# OTHERS.net
KiCad netlist of a schematic drawn in Altium Designer
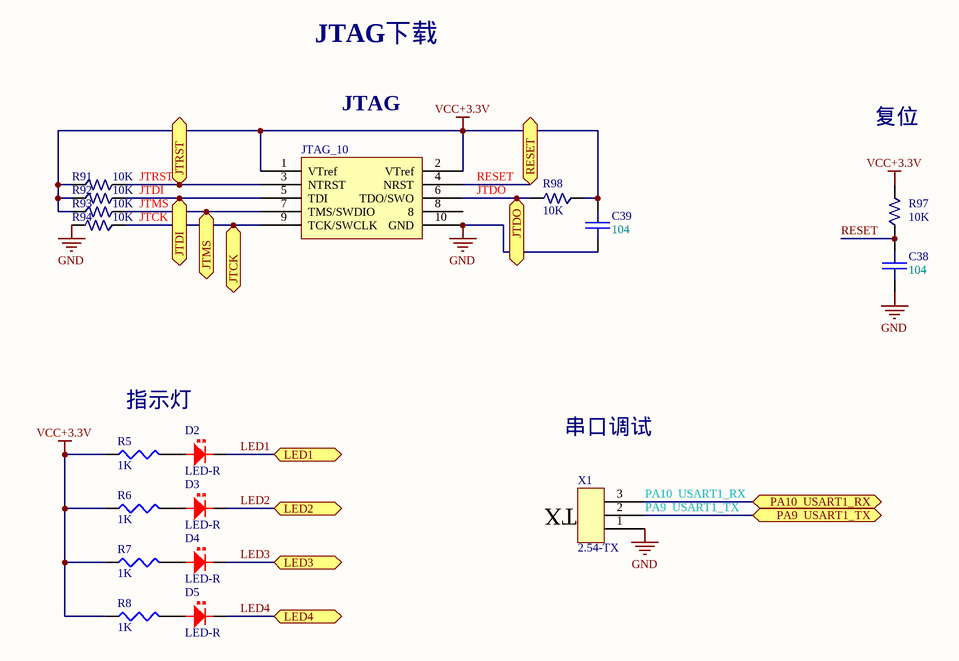
[diagram p0: OTHERS.SchDoc]

(export (version "E")
  (design (tool "Eeschema 10.0.6"))
  (components
    (comp (ref "C38")
      (value "104")
      (footprint "0603")
      (description "陶瓷电容")
      (libsource (lib "8CF_V6") (part "CAP"))
    )
    (comp (ref "C39")
      (value "104")
      (footprint "0603")
      (description "陶瓷电容")
      (libsource (lib "8CF_V6") (part "CAP"))
    )
    (comp (ref "D2")
      (value "LED-R")
      (footprint "LED-0603")
      (description "红色LED")
      (libsource (lib "mylib") (part "LED-RED"))
    )
    (comp (ref "D3")
      (value "LED-R")
      (footprint "LED-0603")
      (description "红色LED")
      (libsource (lib "mylib") (part "LED-RED"))
    )
    (comp (ref "D4")
      (value "LED-R")
      (footprint "LED-0603")
      (description "红色LED")
      (libsource (lib "mylib") (part "LED-RED"))
    )
    (comp (ref "D5")
      (value "LED-R")
      (footprint "LED-0603")
      (description "红色LED")
      (libsource (lib "mylib") (part "LED-RED"))
    )
    (comp (ref "JTAG") (value "JTAG_10") (footprint "JTAG_10") (libsource (lib "mylib") (part "JTAG_10")))
    (comp (ref "R5") (value "1K") (footprint "0603") (libsource (lib "INSPUR_SCH") (part "RES1")))
    (comp (ref "R6") (value "1K") (footprint "0603") (libsource (lib "INSPUR_SCH") (part "RES1")))
    (comp (ref "R7") (value "1K") (footprint "0603") (libsource (lib "INSPUR_SCH") (part "RES1")))
    (comp (ref "R8") (value "1K") (footprint "0603") (libsource (lib "INSPUR_SCH") (part "RES1")))
    (comp (ref "R91")
      (value "10K")
      (footprint "0603")
      (description "高精度电阻")
      (libsource (lib "8CF_V6") (part "RES-1%"))
    )
    (comp (ref "R92")
      (value "10K")
      (footprint "0603")
      (description "高精度电阻")
      (libsource (lib "8CF_V6") (part "RES-1%"))
    )
    (comp (ref "R93")
      (value "10K")
      (footprint "0603")
      (description "高精度电阻")
      (libsource (lib "8CF_V6") (part "RES-1%"))
    )
    (comp (ref "R94")
      (value "10K")
      (footprint "0603")
      (description "高精度电阻")
      (libsource (lib "8CF_V6") (part "RES-1%"))
    )
    (comp (ref "R97")
      (value "10K")
      (footprint "0603")
      (description "高精度电阻")
      (libsource (lib "8CF_V6") (part "RES-1%"))
    )
    (comp (ref "R98")
      (value "10K")
      (footprint "0603")
      (description "高精度电阻")
      (libsource (lib "8CF_V6") (part "RES-1%"))
    )
    (comp (ref "X1") (value "2.54-TX") (footprint "2.54-TX") (libsource (lib "INSPUR_SCH") (part "2.54-TX")))
  )
  (nets
    (net (code "1") (name "/JTCK") (class "Default")
      (node (ref "JTAG") (pin "9") (pinfunction "TCK/SWCLK_9") (pintype "passive"))
      (node (ref "R94") (pin "1") (pintype "passive"))
    )
    (net (code "2") (name "/JTDI") (class "Default")
      (node (ref "JTAG") (pin "5") (pinfunction "TDI_5") (pintype "passive"))
      (node (ref "R92") (pin "2") (pintype "passive"))
    )
    (net (code "3") (name "/JTDO") (class "Default")
      (node (ref "JTAG") (pin "6") (pinfunction "TDO/SWO_6") (pintype "passive"))
      (node (ref "R98") (pin "2") (pintype "passive"))
    )
    (net (code "4") (name "/JTMS") (class "Default")
      (node (ref "JTAG") (pin "7") (pinfunction "TMS/SWDIO_7") (pintype "passive"))
      (node (ref "R93") (pin "2") (pintype "passive"))
    )
    (net (code "5") (name "/JTRST") (class "Default")
      (node (ref "JTAG") (pin "3") (pinfunction "NTRST_3") (pintype "passive"))
      (node (ref "R91") (pin "2") (pintype "passive"))
    )
    (net (code "6") (name "/LED1") (class "Default") (node (ref "D2") (pin "2") (pintype "passive")))
    (net (code "7") (name "/LED2") (class "Default") (node (ref "D3") (pin "2") (pintype "passive")))
    (net (code "8") (name "/LED3") (class "Default") (node (ref "D4") (pin "2") (pintype "passive")))
    (net (code "9") (name "/LED4") (class "Default") (node (ref "D5") (pin "2") (pintype "passive")))
    (net (code "10") (name "/PA9  USART1_TX") (class "Default")
      (node (ref "X1") (pin "2") (pintype "passive"))
    )
    (net (code "11") (name "/PA10  USART1_RX") (class "Default")
      (node (ref "X1") (pin "3") (pintype "passive"))
    )
    (net (code "12") (name "/RESET") (class "Default")
      (node (ref "C38") (pin "2") (pintype "passive"))
      (node (ref "JTAG") (pin "4") (pinfunction "NRST_4") (pintype "passive"))
      (node (ref "R97") (pin "1") (pintype "passive"))
    )
    (net (code "13") (name "GND") (class "Default")
      (node (ref "C38") (pin "1") (pintype "passive"))
      (node (ref "C39") (pin "2") (pintype "passive"))
      (node (ref "JTAG") (pin "10") (pinfunction "GND_10") (pintype "passive"))
      (node (ref "R94") (pin "2") (pintype "passive"))
      (node (ref "X1") (pin "1") (pintype "passive"))
    )
    (net (code "14") (name "Net-(D2-Pad1)") (class "Default")
      (node (ref "D2") (pin "1") (pintype "passive"))
      (node (ref "R5") (pin "2") (pinfunction "2_2") (pintype "passive"))
    )
    (net (code "15") (name "Net-(D3-Pad1)") (class "Default")
      (node (ref "D3") (pin "1") (pintype "passive"))
      (node (ref "R6") (pin "2") (pinfunction "2_2") (pintype "passive"))
    )
    (net (code "16") (name "Net-(D4-Pad1)") (class "Default")
      (node (ref "D4") (pin "1") (pintype "passive"))
      (node (ref "R7") (pin "2") (pinfunction "2_2") (pintype "passive"))
    )
    (net (code "17") (name "Net-(D5-Pad1)") (class "Default")
      (node (ref "D5") (pin "1") (pintype "passive"))
      (node (ref "R8") (pin "2") (pinfunction "2_2") (pintype "passive"))
    )
    (net (code "18") (name "VCC+3.3V") (class "Default")
      (node (ref "C39") (pin "1") (pintype "passive"))
      (node (ref "JTAG") (pin "1") (pinfunction "VTref_1") (pintype "passive"))
      (node (ref "JTAG") (pin "2") (pinfunction "VTref_2") (pintype "passive"))
      (node (ref "R5") (pin "1") (pinfunction "1_1") (pintype "passive"))
      (node (ref "R6") (pin "1") (pinfunction "1_1") (pintype "passive"))
      (node (ref "R7") (pin "1") (pinfunction "1_1") (pintype "passive"))
      (node (ref "R8") (pin "1") (pinfunction "1_1") (pintype "passive"))
      (node (ref "R91") (pin "1") (pintype "passive"))
      (node (ref "R92") (pin "1") (pintype "passive"))
      (node (ref "R93") (pin "1") (pintype "passive"))
      (node (ref "R97") (pin "2") (pintype "passive"))
      (node (ref "R98") (pin "1") (pintype "passive"))
    )
    (net (code "19") (name "unconnected-(JTAG-Pad8)") (class "Default")
      (node (ref "JTAG") (pin "8") (pinfunction "8_8") (pintype "passive"))
    )
  )
)
